# 8bit.net
KiCad netlist of a schematic drawn in EasyEDA
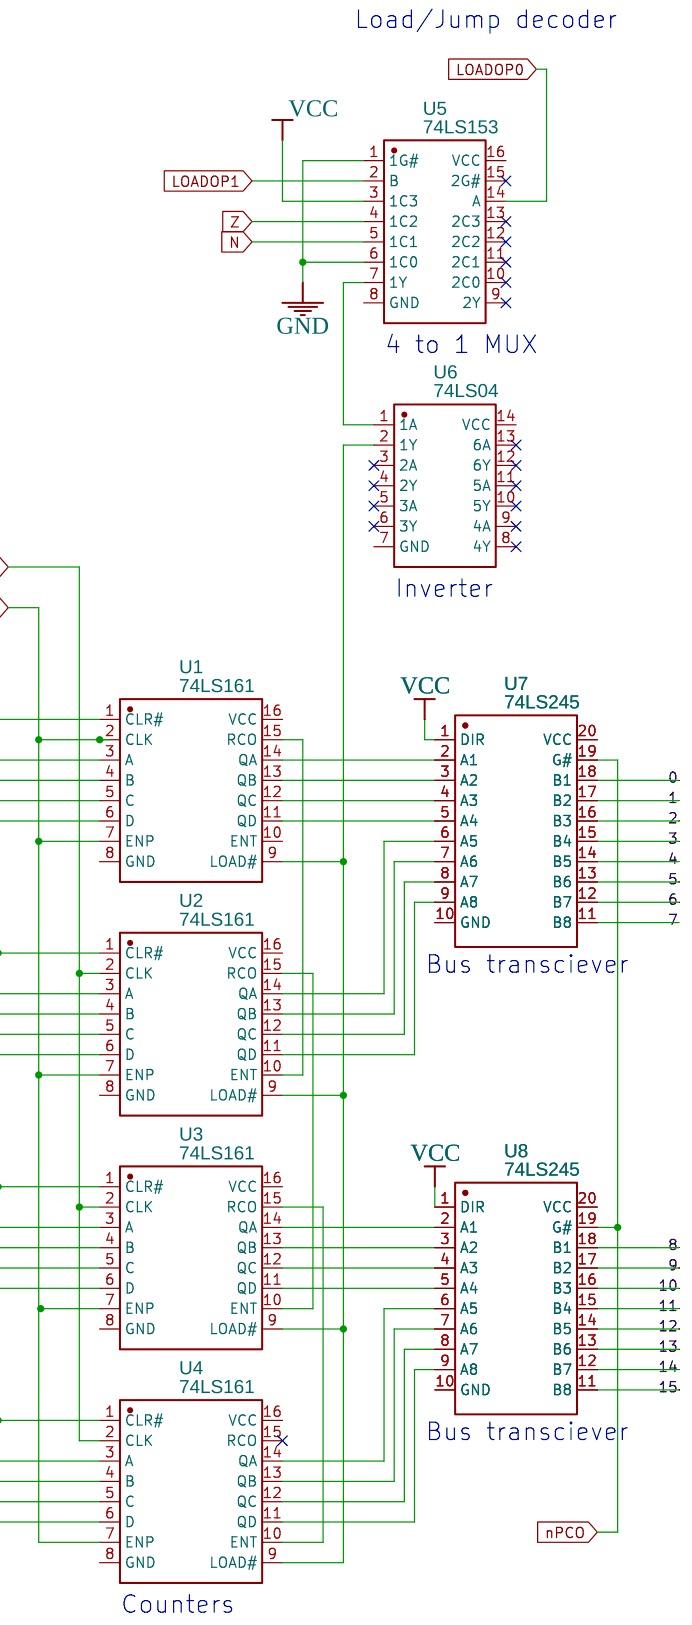
[diagram p0: PC]
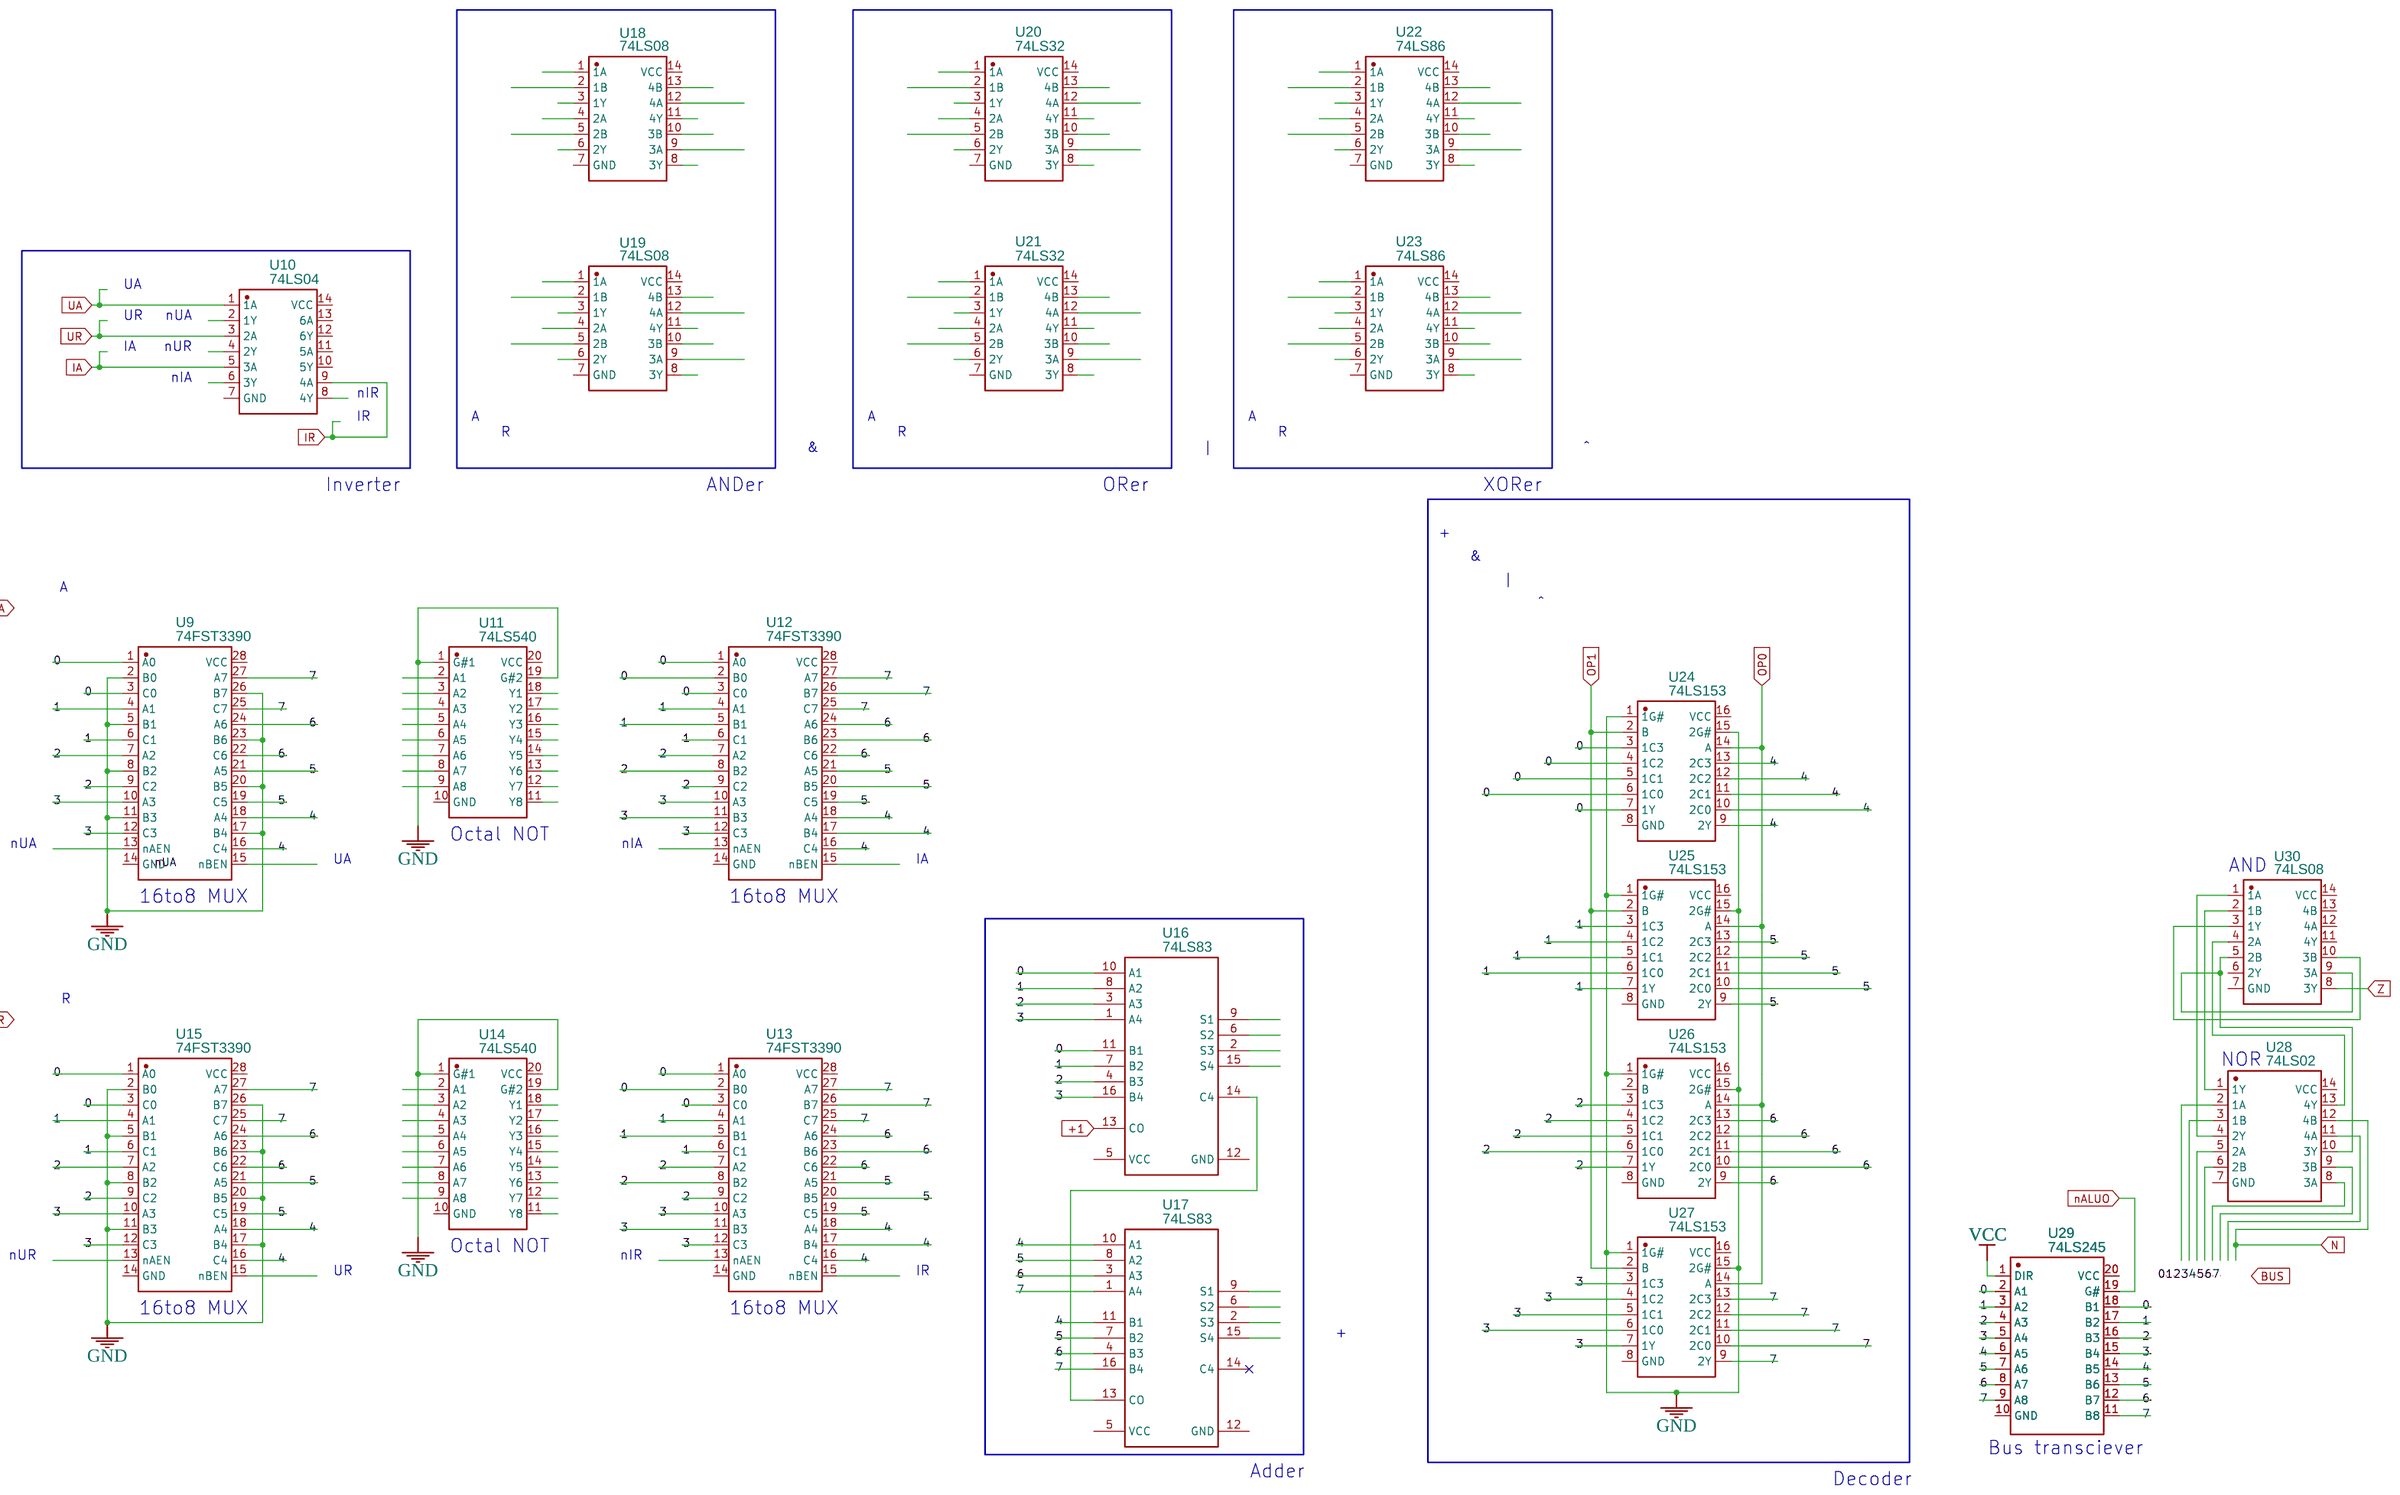
[diagram p1: ALU]

(export (version "E")
  (design (tool "Eeschema 10.0.6"))
  (components
    (comp (ref "U1")
      (value "74LS161")
      (fields
        (field (name "BOM_Manufacturer Part") "SN74LS161AN")
        (field (name "BOM_Supplier Part") "C1547960")
      )
      (libsource (lib "") (part "SN74LS161AN"))
    )
    (comp (ref "U2")
      (value "74LS161")
      (fields
        (field (name "BOM_Manufacturer Part") "SN74LS161AN")
        (field (name "BOM_Supplier Part") "C1547960")
      )
      (libsource (lib "") (part "SN74LS161AN"))
    )
    (comp (ref "U3")
      (value "74LS161")
      (fields
        (field (name "BOM_Manufacturer Part") "SN74LS161AN")
        (field (name "BOM_Supplier Part") "C1547960")
      )
      (libsource (lib "") (part "SN74LS161AN"))
    )
    (comp (ref "U4")
      (value "74LS161")
      (fields
        (field (name "BOM_Manufacturer Part") "SN74LS161AN")
        (field (name "BOM_Supplier Part") "C1547960")
      )
      (libsource (lib "") (part "SN74LS161AN"))
    )
    (comp (ref "U5")
      (value "74LS153")
      (fields
        (field (name "BOM_Manufacturer Part") "SN74LS153N")
        (field (name "BOM_Supplier Part") "C1547278")
      )
      (libsource (lib "") (part "SN74LS153N"))
    )
    (comp (ref "U6")
      (value "74LS04")
      (fields (field (name "BOM_Manufacturer Part") "XL74LS04") (field (name "BOM_Supplier Part") "C513511"))
      (libsource (lib "") (part "XL74LS04"))
    )
    (comp (ref "U7")
      (value "74LS245")
      (fields (field (name "BOM_Manufacturer Part") "74LS245WMX") (field (name "BOM_Supplier Part") "C6034"))
      (libsource (lib "") (part "74LS245WMX"))
    )
    (comp (ref "U8")
      (value "74LS245")
      (fields (field (name "BOM_Manufacturer Part") "74LS245WMX") (field (name "BOM_Supplier Part") "C6034"))
      (libsource (lib "") (part "74LS245WMX"))
    )
    (comp (ref "U9") (value "74FST3390") (libsource (lib "") (part "74FST3390")))
    (comp (ref "U10")
      (value "74LS04")
      (fields (field (name "BOM_Manufacturer Part") "XL74LS04") (field (name "BOM_Supplier Part") "C513511"))
      (libsource (lib "") (part "XL74LS04"))
    )
    (comp (ref "U11")
      (value "74LS540")
      (fields
        (field (name "BOM_Manufacturer Part") "SN74LS540DW")
        (field (name "BOM_Supplier Part") "C1548464")
      )
      (libsource (lib "") (part "SN74LS540DW"))
    )
    (comp (ref "U12") (value "74FST3390") (libsource (lib "") (part "74FST3390")))
    (comp (ref "U13") (value "74FST3390") (libsource (lib "") (part "74FST3390")))
    (comp (ref "U14")
      (value "74LS540")
      (fields
        (field (name "BOM_Manufacturer Part") "SN74LS540DW")
        (field (name "BOM_Supplier Part") "C1548464")
      )
      (libsource (lib "") (part "SN74LS540DW"))
    )
    (comp (ref "U15") (value "74FST3390") (libsource (lib "") (part "74FST3390")))
    (comp (ref "U16") (value "74LS83") (libsource (lib "") (part "HD74LS83AP")))
    (comp (ref "U17") (value "74LS83") (libsource (lib "") (part "HD74LS83AP")))
    (comp (ref "U18")
      (value "74LS08")
      (fields (field (name "BOM_Manufacturer Part") "XL74LS08") (field (name "BOM_Supplier Part") "C521140"))
      (libsource (lib "") (part "XL74LS08"))
    )
    (comp (ref "U19")
      (value "74LS08")
      (fields (field (name "BOM_Manufacturer Part") "XL74LS08") (field (name "BOM_Supplier Part") "C521140"))
      (libsource (lib "") (part "XL74LS08"))
    )
    (comp (ref "U20")
      (value "74LS32")
      (fields
        (field (name "BOM_Manufacturer Part") "SN74LS32D")
        (field (name "BOM_Supplier Part") "C2869302")
      )
      (libsource (lib "") (part "SN74LS32D"))
    )
    (comp (ref "U21")
      (value "74LS32")
      (fields
        (field (name "BOM_Manufacturer Part") "SN74LS32D")
        (field (name "BOM_Supplier Part") "C2869302")
      )
      (libsource (lib "") (part "SN74LS32D"))
    )
    (comp (ref "U22")
      (value "74LS86")
      (fields (field (name "BOM_Manufacturer Part") "XD74LS86") (field (name "BOM_Supplier Part") "C556290"))
      (libsource (lib "") (part "XD74LS86"))
    )
    (comp (ref "U23")
      (value "74LS86")
      (fields (field (name "BOM_Manufacturer Part") "XD74LS86") (field (name "BOM_Supplier Part") "C556290"))
      (libsource (lib "") (part "XD74LS86"))
    )
    (comp (ref "U24")
      (value "74LS153")
      (fields
        (field (name "BOM_Manufacturer Part") "SN74LS153D")
        (field (name "BOM_Supplier Part") "C1547147")
      )
      (libsource (lib "") (part "SN74LS153D"))
    )
    (comp (ref "U25")
      (value "74LS153")
      (fields
        (field (name "BOM_Manufacturer Part") "SN74LS153D")
        (field (name "BOM_Supplier Part") "C1547147")
      )
      (libsource (lib "") (part "SN74LS153D"))
    )
    (comp (ref "U26")
      (value "74LS153")
      (fields
        (field (name "BOM_Manufacturer Part") "SN74LS153D")
        (field (name "BOM_Supplier Part") "C1547147")
      )
      (libsource (lib "") (part "SN74LS153D"))
    )
    (comp (ref "U27")
      (value "74LS153")
      (fields
        (field (name "BOM_Manufacturer Part") "SN74LS153D")
        (field (name "BOM_Supplier Part") "C1547147")
      )
      (libsource (lib "") (part "SN74LS153D"))
    )
    (comp (ref "U28")
      (value "74LS02")
      (fields
        (field (name "BOM_Manufacturer Part") "SN74LS02D")
        (field (name "BOM_Supplier Part") "C2878666")
      )
      (libsource (lib "") (part "SN74LS02D"))
    )
    (comp (ref "U29")
      (value "74LS245")
      (fields (field (name "BOM_Manufacturer Part") "74LS245WMX") (field (name "BOM_Supplier Part") "C6034"))
      (libsource (lib "") (part "74LS245WMX"))
    )
    (comp (ref "U30")
      (value "74LS08")
      (fields (field (name "BOM_Manufacturer Part") "XL74LS08") (field (name "BOM_Supplier Part") "C521140"))
      (libsource (lib "") (part "XL74LS08"))
    )
  )
  (nets
    (net (code "1") (name "+1") (class "Default")
      (node (ref "U16") (pin "13") (pinfunction "CO_13") (pintype "unspecified"))
    )
    (net (code "2") (name "0") (class "Default")
      (node (ref "U1") (pin "3") (pinfunction "A_3") (pintype "unspecified"))
      (node (ref "U12") (pin "1") (pinfunction "A0_1") (pintype "unspecified"))
      (node (ref "U12") (pin "2") (pinfunction "B0_2") (pintype "unspecified"))
      (node (ref "U12") (pin "3") (pinfunction "C0_3") (pintype "unspecified"))
      (node (ref "U13") (pin "1") (pinfunction "A0_1") (pintype "unspecified"))
      (node (ref "U13") (pin "2") (pinfunction "B0_2") (pintype "unspecified"))
      (node (ref "U13") (pin "3") (pinfunction "C0_3") (pintype "unspecified"))
      (node (ref "U15") (pin "1") (pinfunction "A0_1") (pintype "unspecified"))
      (node (ref "U15") (pin "3") (pinfunction "C0_3") (pintype "unspecified"))
      (node (ref "U16") (pin "10") (pinfunction "A1_10") (pintype "unspecified"))
      (node (ref "U16") (pin "11") (pinfunction "B1_11") (pintype "unspecified"))
      (node (ref "U24") (pin "3") (pinfunction "1C3_3") (pintype "unspecified"))
      (node (ref "U24") (pin "4") (pinfunction "1C2_4") (pintype "unspecified"))
      (node (ref "U24") (pin "5") (pinfunction "1C1_5") (pintype "unspecified"))
      (node (ref "U24") (pin "6") (pinfunction "1C0_6") (pintype "unspecified"))
      (node (ref "U24") (pin "7") (pinfunction "1Y_7") (pintype "unspecified"))
      (node (ref "U29") (pin "18") (pinfunction "B1_18") (pintype "unspecified"))
      (node (ref "U29") (pin "2") (pinfunction "A1_2") (pintype "unspecified"))
      (node (ref "U7") (pin "18") (pinfunction "B1_18") (pintype "unspecified"))
      (node (ref "U9") (pin "1") (pinfunction "A0_1") (pintype "unspecified"))
      (node (ref "U9") (pin "3") (pinfunction "C0_3") (pintype "unspecified"))
    )
    (net (code "3") (name "1") (class "Default")
      (node (ref "U1") (pin "4") (pinfunction "B_4") (pintype "unspecified"))
      (node (ref "U12") (pin "4") (pinfunction "A1_4") (pintype "unspecified"))
      (node (ref "U12") (pin "5") (pinfunction "B1_5") (pintype "unspecified"))
      (node (ref "U12") (pin "6") (pinfunction "C1_6") (pintype "unspecified"))
      (node (ref "U13") (pin "4") (pinfunction "A1_4") (pintype "unspecified"))
      (node (ref "U13") (pin "5") (pinfunction "B1_5") (pintype "unspecified"))
      (node (ref "U13") (pin "6") (pinfunction "C1_6") (pintype "unspecified"))
      (node (ref "U15") (pin "4") (pinfunction "A1_4") (pintype "unspecified"))
      (node (ref "U15") (pin "6") (pinfunction "C1_6") (pintype "unspecified"))
      (node (ref "U16") (pin "7") (pinfunction "B2_7") (pintype "unspecified"))
      (node (ref "U16") (pin "8") (pinfunction "A2_8") (pintype "unspecified"))
      (node (ref "U25") (pin "3") (pinfunction "1C3_3") (pintype "unspecified"))
      (node (ref "U25") (pin "4") (pinfunction "1C2_4") (pintype "unspecified"))
      (node (ref "U25") (pin "5") (pinfunction "1C1_5") (pintype "unspecified"))
      (node (ref "U25") (pin "6") (pinfunction "1C0_6") (pintype "unspecified"))
      (node (ref "U25") (pin "7") (pinfunction "1Y_7") (pintype "unspecified"))
      (node (ref "U29") (pin "17") (pinfunction "B2_17") (pintype "unspecified"))
      (node (ref "U29") (pin "3") (pinfunction "A2_3") (pintype "unspecified"))
      (node (ref "U7") (pin "17") (pinfunction "B2_17") (pintype "unspecified"))
      (node (ref "U9") (pin "4") (pinfunction "A1_4") (pintype "unspecified"))
      (node (ref "U9") (pin "6") (pinfunction "C1_6") (pintype "unspecified"))
    )
    (net (code "4") (name "2") (class "Default")
      (node (ref "U1") (pin "5") (pinfunction "C_5") (pintype "unspecified"))
      (node (ref "U12") (pin "7") (pinfunction "A2_7") (pintype "unspecified"))
      (node (ref "U12") (pin "8") (pinfunction "B2_8") (pintype "unspecified"))
      (node (ref "U12") (pin "9") (pinfunction "C2_9") (pintype "unspecified"))
      (node (ref "U13") (pin "7") (pinfunction "A2_7") (pintype "unspecified"))
      (node (ref "U13") (pin "8") (pinfunction "B2_8") (pintype "unspecified"))
      (node (ref "U13") (pin "9") (pinfunction "C2_9") (pintype "unspecified"))
      (node (ref "U15") (pin "7") (pinfunction "A2_7") (pintype "unspecified"))
      (node (ref "U15") (pin "9") (pinfunction "C2_9") (pintype "unspecified"))
      (node (ref "U16") (pin "3") (pinfunction "A3_3") (pintype "unspecified"))
      (node (ref "U16") (pin "4") (pinfunction "B3_4") (pintype "unspecified"))
      (node (ref "U26") (pin "3") (pinfunction "1C3_3") (pintype "unspecified"))
      (node (ref "U26") (pin "4") (pinfunction "1C2_4") (pintype "unspecified"))
      (node (ref "U26") (pin "5") (pinfunction "1C1_5") (pintype "unspecified"))
      (node (ref "U26") (pin "6") (pinfunction "1C0_6") (pintype "unspecified"))
      (node (ref "U26") (pin "7") (pinfunction "1Y_7") (pintype "unspecified"))
      (node (ref "U29") (pin "16") (pinfunction "B3_16") (pintype "unspecified"))
      (node (ref "U29") (pin "4") (pinfunction "A3_4") (pintype "unspecified"))
      (node (ref "U7") (pin "16") (pinfunction "B3_16") (pintype "unspecified"))
      (node (ref "U9") (pin "7") (pinfunction "A2_7") (pintype "unspecified"))
      (node (ref "U9") (pin "9") (pinfunction "C2_9") (pintype "unspecified"))
    )
    (net (code "5") (name "3") (class "Default")
      (node (ref "U1") (pin "6") (pinfunction "D_6") (pintype "unspecified"))
      (node (ref "U12") (pin "10") (pinfunction "A3_10") (pintype "unspecified"))
      (node (ref "U12") (pin "11") (pinfunction "B3_11") (pintype "unspecified"))
      (node (ref "U12") (pin "12") (pinfunction "C3_12") (pintype "unspecified"))
      (node (ref "U13") (pin "10") (pinfunction "A3_10") (pintype "unspecified"))
      (node (ref "U13") (pin "11") (pinfunction "B3_11") (pintype "unspecified"))
      (node (ref "U13") (pin "12") (pinfunction "C3_12") (pintype "unspecified"))
      (node (ref "U15") (pin "10") (pinfunction "A3_10") (pintype "unspecified"))
      (node (ref "U15") (pin "12") (pinfunction "C3_12") (pintype "unspecified"))
      (node (ref "U16") (pin "1") (pinfunction "A4_1") (pintype "unspecified"))
      (node (ref "U16") (pin "16") (pinfunction "B4_16") (pintype "unspecified"))
      (node (ref "U27") (pin "3") (pinfunction "1C3_3") (pintype "unspecified"))
      (node (ref "U27") (pin "4") (pinfunction "1C2_4") (pintype "unspecified"))
      (node (ref "U27") (pin "5") (pinfunction "1C1_5") (pintype "unspecified"))
      (node (ref "U27") (pin "6") (pinfunction "1C0_6") (pintype "unspecified"))
      (node (ref "U27") (pin "7") (pinfunction "1Y_7") (pintype "unspecified"))
      (node (ref "U29") (pin "15") (pinfunction "B4_15") (pintype "unspecified"))
      (node (ref "U29") (pin "5") (pinfunction "A4_5") (pintype "unspecified"))
      (node (ref "U7") (pin "15") (pinfunction "B4_15") (pintype "unspecified"))
      (node (ref "U9") (pin "10") (pinfunction "A3_10") (pintype "unspecified"))
      (node (ref "U9") (pin "12") (pinfunction "C3_12") (pintype "unspecified"))
    )
    (net (code "6") (name "4") (class "Default")
      (node (ref "U12") (pin "16") (pinfunction "C4_16") (pintype "unspecified"))
      (node (ref "U12") (pin "17") (pinfunction "B4_17") (pintype "unspecified"))
      (node (ref "U12") (pin "18") (pinfunction "A4_18") (pintype "unspecified"))
      (node (ref "U13") (pin "16") (pinfunction "C4_16") (pintype "unspecified"))
      (node (ref "U13") (pin "17") (pinfunction "B4_17") (pintype "unspecified"))
      (node (ref "U13") (pin "18") (pinfunction "A4_18") (pintype "unspecified"))
      (node (ref "U15") (pin "16") (pinfunction "C4_16") (pintype "unspecified"))
      (node (ref "U15") (pin "18") (pinfunction "A4_18") (pintype "unspecified"))
      (node (ref "U17") (pin "10") (pinfunction "A1_10") (pintype "unspecified"))
      (node (ref "U17") (pin "11") (pinfunction "B1_11") (pintype "unspecified"))
      (node (ref "U2") (pin "3") (pinfunction "A_3") (pintype "unspecified"))
      (node (ref "U24") (pin "10") (pinfunction "2C0_10") (pintype "unspecified"))
      (node (ref "U24") (pin "11") (pinfunction "2C1_11") (pintype "unspecified"))
      (node (ref "U24") (pin "12") (pinfunction "2C2_12") (pintype "unspecified"))
      (node (ref "U24") (pin "13") (pinfunction "2C3_13") (pintype "unspecified"))
      (node (ref "U24") (pin "9") (pinfunction "2Y_9") (pintype "unspecified"))
      (node (ref "U29") (pin "14") (pinfunction "B5_14") (pintype "unspecified"))
      (node (ref "U29") (pin "6") (pinfunction "A5_6") (pintype "unspecified"))
      (node (ref "U7") (pin "14") (pinfunction "B5_14") (pintype "unspecified"))
      (node (ref "U9") (pin "16") (pinfunction "C4_16") (pintype "unspecified"))
      (node (ref "U9") (pin "18") (pinfunction "A4_18") (pintype "unspecified"))
    )
    (net (code "7") (name "5") (class "Default")
      (node (ref "U12") (pin "19") (pinfunction "C5_19") (pintype "unspecified"))
      (node (ref "U12") (pin "20") (pinfunction "B5_20") (pintype "unspecified"))
      (node (ref "U12") (pin "21") (pinfunction "A5_21") (pintype "unspecified"))
      (node (ref "U13") (pin "19") (pinfunction "C5_19") (pintype "unspecified"))
      (node (ref "U13") (pin "20") (pinfunction "B5_20") (pintype "unspecified"))
      (node (ref "U13") (pin "21") (pinfunction "A5_21") (pintype "unspecified"))
      (node (ref "U15") (pin "19") (pinfunction "C5_19") (pintype "unspecified"))
      (node (ref "U15") (pin "21") (pinfunction "A5_21") (pintype "unspecified"))
      (node (ref "U17") (pin "7") (pinfunction "B2_7") (pintype "unspecified"))
      (node (ref "U17") (pin "8") (pinfunction "A2_8") (pintype "unspecified"))
      (node (ref "U2") (pin "4") (pinfunction "B_4") (pintype "unspecified"))
      (node (ref "U25") (pin "10") (pinfunction "2C0_10") (pintype "unspecified"))
      (node (ref "U25") (pin "11") (pinfunction "2C1_11") (pintype "unspecified"))
      (node (ref "U25") (pin "12") (pinfunction "2C2_12") (pintype "unspecified"))
      (node (ref "U25") (pin "13") (pinfunction "2C3_13") (pintype "unspecified"))
      (node (ref "U25") (pin "9") (pinfunction "2Y_9") (pintype "unspecified"))
      (node (ref "U29") (pin "13") (pinfunction "B6_13") (pintype "unspecified"))
      (node (ref "U29") (pin "7") (pinfunction "A6_7") (pintype "unspecified"))
      (node (ref "U7") (pin "13") (pinfunction "B6_13") (pintype "unspecified"))
      (node (ref "U9") (pin "19") (pinfunction "C5_19") (pintype "unspecified"))
      (node (ref "U9") (pin "21") (pinfunction "A5_21") (pintype "unspecified"))
    )
    (net (code "8") (name "6") (class "Default")
      (node (ref "U12") (pin "22") (pinfunction "C6_22") (pintype "unspecified"))
      (node (ref "U12") (pin "23") (pinfunction "B6_23") (pintype "unspecified"))
      (node (ref "U12") (pin "24") (pinfunction "A6_24") (pintype "unspecified"))
      (node (ref "U13") (pin "22") (pinfunction "C6_22") (pintype "unspecified"))
      (node (ref "U13") (pin "23") (pinfunction "B6_23") (pintype "unspecified"))
      (node (ref "U13") (pin "24") (pinfunction "A6_24") (pintype "unspecified"))
      (node (ref "U15") (pin "22") (pinfunction "C6_22") (pintype "unspecified"))
      (node (ref "U15") (pin "24") (pinfunction "A6_24") (pintype "unspecified"))
      (node (ref "U17") (pin "3") (pinfunction "A3_3") (pintype "unspecified"))
      (node (ref "U17") (pin "4") (pinfunction "B3_4") (pintype "unspecified"))
      (node (ref "U2") (pin "5") (pinfunction "C_5") (pintype "unspecified"))
      (node (ref "U26") (pin "10") (pinfunction "2C0_10") (pintype "unspecified"))
      (node (ref "U26") (pin "11") (pinfunction "2C1_11") (pintype "unspecified"))
      (node (ref "U26") (pin "12") (pinfunction "2C2_12") (pintype "unspecified"))
      (node (ref "U26") (pin "13") (pinfunction "2C3_13") (pintype "unspecified"))
      (node (ref "U26") (pin "9") (pinfunction "2Y_9") (pintype "unspecified"))
      (node (ref "U29") (pin "12") (pinfunction "B7_12") (pintype "unspecified"))
      (node (ref "U29") (pin "8") (pinfunction "A7_8") (pintype "unspecified"))
      (node (ref "U7") (pin "12") (pinfunction "B7_12") (pintype "unspecified"))
      (node (ref "U9") (pin "22") (pinfunction "C6_22") (pintype "unspecified"))
      (node (ref "U9") (pin "24") (pinfunction "A6_24") (pintype "unspecified"))
    )
    (net (code "9") (name "7") (class "Default")
      (node (ref "U12") (pin "25") (pinfunction "C7_25") (pintype "unspecified"))
      (node (ref "U12") (pin "26") (pinfunction "B7_26") (pintype "unspecified"))
      (node (ref "U12") (pin "27") (pinfunction "A7_27") (pintype "unspecified"))
      (node (ref "U13") (pin "25") (pinfunction "C7_25") (pintype "unspecified"))
      (node (ref "U13") (pin "26") (pinfunction "B7_26") (pintype "unspecified"))
      (node (ref "U13") (pin "27") (pinfunction "A7_27") (pintype "unspecified"))
      (node (ref "U15") (pin "25") (pinfunction "C7_25") (pintype "unspecified"))
      (node (ref "U15") (pin "27") (pinfunction "A7_27") (pintype "unspecified"))
      (node (ref "U17") (pin "1") (pinfunction "A4_1") (pintype "unspecified"))
      (node (ref "U17") (pin "16") (pinfunction "B4_16") (pintype "unspecified"))
      (node (ref "U2") (pin "6") (pinfunction "D_6") (pintype "unspecified"))
      (node (ref "U27") (pin "10") (pinfunction "2C0_10") (pintype "unspecified"))
      (node (ref "U27") (pin "11") (pinfunction "2C1_11") (pintype "unspecified"))
      (node (ref "U27") (pin "12") (pinfunction "2C2_12") (pintype "unspecified"))
      (node (ref "U27") (pin "13") (pinfunction "2C3_13") (pintype "unspecified"))
      (node (ref "U27") (pin "9") (pinfunction "2Y_9") (pintype "unspecified"))
      (node (ref "U29") (pin "11") (pinfunction "B8_11") (pintype "unspecified"))
      (node (ref "U29") (pin "9") (pinfunction "A8_9") (pintype "unspecified"))
      (node (ref "U7") (pin "11") (pinfunction "B8_11") (pintype "unspecified"))
      (node (ref "U9") (pin "25") (pinfunction "C7_25") (pintype "unspecified"))
      (node (ref "U9") (pin "27") (pinfunction "A7_27") (pintype "unspecified"))
    )
    (net (code "10") (name "8") (class "Default")
      (node (ref "U3") (pin "3") (pinfunction "A_3") (pintype "unspecified"))
      (node (ref "U8") (pin "18") (pinfunction "B1_18") (pintype "unspecified"))
    )
    (net (code "11") (name "9") (class "Default")
      (node (ref "U3") (pin "4") (pinfunction "B_4") (pintype "unspecified"))
      (node (ref "U8") (pin "17") (pinfunction "B2_17") (pintype "unspecified"))
    )
    (net (code "12") (name "10") (class "Default")
      (node (ref "U3") (pin "5") (pinfunction "C_5") (pintype "unspecified"))
      (node (ref "U8") (pin "16") (pinfunction "B3_16") (pintype "unspecified"))
    )
    (net (code "13") (name "11") (class "Default")
      (node (ref "U3") (pin "6") (pinfunction "D_6") (pintype "unspecified"))
      (node (ref "U8") (pin "15") (pinfunction "B4_15") (pintype "unspecified"))
    )
    (net (code "14") (name "12") (class "Default")
      (node (ref "U4") (pin "3") (pinfunction "A_3") (pintype "unspecified"))
      (node (ref "U8") (pin "14") (pinfunction "B5_14") (pintype "unspecified"))
    )
    (net (code "15") (name "13") (class "Default")
      (node (ref "U4") (pin "4") (pinfunction "B_4") (pintype "unspecified"))
      (node (ref "U8") (pin "13") (pinfunction "B6_13") (pintype "unspecified"))
    )
    (net (code "16") (name "14") (class "Default")
      (node (ref "U4") (pin "5") (pinfunction "C_5") (pintype "unspecified"))
      (node (ref "U8") (pin "12") (pinfunction "B7_12") (pintype "unspecified"))
    )
    (net (code "17") (name "15") (class "Default")
      (node (ref "U4") (pin "6") (pinfunction "D_6") (pintype "unspecified"))
      (node (ref "U8") (pin "11") (pinfunction "B8_11") (pintype "unspecified"))
    )
    (net (code "20") (name "CLK") (class "Default")
      (node (ref "U2") (pin "2") (pinfunction "CLK_2") (pintype "unspecified"))
      (node (ref "U3") (pin "2") (pinfunction "CLK_2") (pintype "unspecified"))
      (node (ref "U4") (pin "2") (pinfunction "CLK_2") (pintype "unspecified"))
    )
    (net (code "21") (name "GND") (class "Default")
      (node (ref "U11") (pin "1") (pinfunction "G#1_1") (pintype "unspecified"))
      (node (ref "U11") (pin "19") (pinfunction "G#2_19") (pintype "unspecified"))
      (node (ref "U14") (pin "1") (pinfunction "G#1_1") (pintype "unspecified"))
      (node (ref "U14") (pin "19") (pinfunction "G#2_19") (pintype "unspecified"))
      (node (ref "U15") (pin "11") (pinfunction "B3_11") (pintype "unspecified"))
      (node (ref "U15") (pin "17") (pinfunction "B4_17") (pintype "unspecified"))
      (node (ref "U15") (pin "2") (pinfunction "B0_2") (pintype "unspecified"))
      (node (ref "U15") (pin "20") (pinfunction "B5_20") (pintype "unspecified"))
      (node (ref "U15") (pin "23") (pinfunction "B6_23") (pintype "unspecified"))
      (node (ref "U15") (pin "26") (pinfunction "B7_26") (pintype "unspecified"))
      (node (ref "U15") (pin "5") (pinfunction "B1_5") (pintype "unspecified"))
      (node (ref "U15") (pin "8") (pinfunction "B2_8") (pintype "unspecified"))
      (node (ref "U24") (pin "1") (pinfunction "1G#_1") (pintype "unspecified"))
      (node (ref "U24") (pin "15") (pinfunction "2G#_15") (pintype "unspecified"))
      (node (ref "U25") (pin "1") (pinfunction "1G#_1") (pintype "unspecified"))
      (node (ref "U25") (pin "15") (pinfunction "2G#_15") (pintype "unspecified"))
      (node (ref "U26") (pin "1") (pinfunction "1G#_1") (pintype "unspecified"))
      (node (ref "U26") (pin "15") (pinfunction "2G#_15") (pintype "unspecified"))
      (node (ref "U27") (pin "1") (pinfunction "1G#_1") (pintype "unspecified"))
      (node (ref "U27") (pin "15") (pinfunction "2G#_15") (pintype "unspecified"))
      (node (ref "U5") (pin "1") (pinfunction "1G#_1") (pintype "unspecified"))
      (node (ref "U5") (pin "6") (pinfunction "1C0_6") (pintype "unspecified"))
      (node (ref "U9") (pin "11") (pinfunction "B3_11") (pintype "unspecified"))
      (node (ref "U9") (pin "17") (pinfunction "B4_17") (pintype "unspecified"))
      (node (ref "U9") (pin "2") (pinfunction "B0_2") (pintype "unspecified"))
      (node (ref "U9") (pin "20") (pinfunction "B5_20") (pintype "unspecified"))
      (node (ref "U9") (pin "23") (pinfunction "B6_23") (pintype "unspecified"))
      (node (ref "U9") (pin "26") (pinfunction "B7_26") (pintype "unspecified"))
      (node (ref "U9") (pin "5") (pinfunction "B1_5") (pintype "unspecified"))
      (node (ref "U9") (pin "8") (pinfunction "B2_8") (pintype "unspecified"))
    )
    (net (code "22") (name "IA") (class "Default")
      (node (ref "U10") (pin "5") (pinfunction "3A_5") (pintype "unspecified"))
    )
    (net (code "23") (name "INC") (class "Default")
      (node (ref "U1") (pin "2") (pinfunction "CLK_2") (pintype "unspecified"))
      (node (ref "U1") (pin "7") (pinfunction "ENP_7") (pintype "unspecified"))
      (node (ref "U2") (pin "7") (pinfunction "ENP_7") (pintype "unspecified"))
      (node (ref "U3") (pin "7") (pinfunction "ENP_7") (pintype "unspecified"))
      (node (ref "U4") (pin "7") (pinfunction "ENP_7") (pintype "unspecified"))
    )
    (net (code "24") (name "IR") (class "Default")
      (node (ref "U10") (pin "9") (pinfunction "4A_9") (pintype "unspecified"))
    )
    (net (code "25") (name "LOADOP0") (class "Default")
      (node (ref "U5") (pin "14") (pinfunction "A_14") (pintype "unspecified"))
    )
    (net (code "26") (name "LOADOP1") (class "Default")
      (node (ref "U5") (pin "2") (pinfunction "B_2") (pintype "unspecified"))
    )
    (net (code "27") (name "N") (class "Default")
      (node (ref "U28") (pin "12") (pinfunction "4B_12") (pintype "unspecified"))
      (node (ref "U5") (pin "5") (pinfunction "1C1_5") (pintype "unspecified"))
    )
    (net (code "28") (name "Net-(U1-LOAD#)") (class "Default")
      (node (ref "U1") (pin "9") (pinfunction "LOAD#_9") (pintype "unspecified"))
      (node (ref "U2") (pin "9") (pinfunction "LOAD#_9") (pintype "unspecified"))
      (node (ref "U3") (pin "9") (pinfunction "LOAD#_9") (pintype "unspecified"))
      (node (ref "U4") (pin "9") (pinfunction "LOAD#_9") (pintype "unspecified"))
      (node (ref "U6") (pin "2") (pinfunction "1Y_2") (pintype "unspecified"))
    )
    (net (code "29") (name "Net-(U1-QA)") (class "Default")
      (node (ref "U1") (pin "14") (pinfunction "QA_14") (pintype "unspecified"))
      (node (ref "U7") (pin "2") (pinfunction "A1_2") (pintype "unspecified"))
    )
    (net (code "30") (name "Net-(U1-QB)") (class "Default")
      (node (ref "U1") (pin "13") (pinfunction "QB_13") (pintype "unspecified"))
      (node (ref "U7") (pin "3") (pinfunction "A2_3") (pintype "unspecified"))
    )
    (net (code "31") (name "Net-(U1-QC)") (class "Default")
      (node (ref "U1") (pin "12") (pinfunction "QC_12") (pintype "unspecified"))
      (node (ref "U7") (pin "4") (pinfunction "A3_4") (pintype "unspecified"))
    )
    (net (code "32") (name "Net-(U1-QD)") (class "Default")
      (node (ref "U1") (pin "11") (pinfunction "QD_11") (pintype "unspecified"))
      (node (ref "U7") (pin "5") (pinfunction "A4_5") (pintype "unspecified"))
    )
    (net (code "33") (name "Net-(U1-RCO)") (class "Default")
      (node (ref "U1") (pin "15") (pinfunction "RCO_15") (pintype "unspecified"))
      (node (ref "U2") (pin "10") (pinfunction "ENT_10") (pintype "unspecified"))
    )
    (net (code "34") (name "Net-(U2-QA)") (class "Default")
      (node (ref "U2") (pin "14") (pinfunction "QA_14") (pintype "unspecified"))
      (node (ref "U7") (pin "6") (pinfunction "A5_6") (pintype "unspecified"))
    )
    (net (code "35") (name "Net-(U2-QB)") (class "Default")
      (node (ref "U2") (pin "13") (pinfunction "QB_13") (pintype "unspecified"))
      (node (ref "U7") (pin "7") (pinfunction "A6_7") (pintype "unspecified"))
    )
    (net (code "36") (name "Net-(U2-QC)") (class "Default")
      (node (ref "U2") (pin "12") (pinfunction "QC_12") (pintype "unspecified"))
      (node (ref "U7") (pin "8") (pinfunction "A7_8") (pintype "unspecified"))
    )
    (net (code "37") (name "Net-(U2-QD)") (class "Default")
      (node (ref "U2") (pin "11") (pinfunction "QD_11") (pintype "unspecified"))
      (node (ref "U7") (pin "9") (pinfunction "A8_9") (pintype "unspecified"))
    )
    (net (code "38") (name "Net-(U2-RCO)") (class "Default")
      (node (ref "U2") (pin "15") (pinfunction "RCO_15") (pintype "unspecified"))
      (node (ref "U3") (pin "10") (pinfunction "ENT_10") (pintype "unspecified"))
    )
    (net (code "39") (name "Net-(U3-QA)") (class "Default")
      (node (ref "U3") (pin "14") (pinfunction "QA_14") (pintype "unspecified"))
      (node (ref "U8") (pin "2") (pinfunction "A1_2") (pintype "unspecified"))
    )
    (net (code "40") (name "Net-(U3-QB)") (class "Default")
      (node (ref "U3") (pin "13") (pinfunction "QB_13") (pintype "unspecified"))
      (node (ref "U8") (pin "3") (pinfunction "A2_3") (pintype "unspecified"))
    )
    (net (code "41") (name "Net-(U3-QC)") (class "Default")
      (node (ref "U3") (pin "12") (pinfunction "QC_12") (pintype "unspecified"))
      (node (ref "U8") (pin "4") (pinfunction "A3_4") (pintype "unspecified"))
    )
    (net (code "42") (name "Net-(U3-QD)") (class "Default")
      (node (ref "U3") (pin "11") (pinfunction "QD_11") (pintype "unspecified"))
      (node (ref "U8") (pin "5") (pinfunction "A4_5") (pintype "unspecified"))
    )
    (net (code "43") (name "Net-(U3-RCO)") (class "Default")
      (node (ref "U3") (pin "15") (pinfunction "RCO_15") (pintype "unspecified"))
      (node (ref "U4") (pin "10") (pinfunction "ENT_10") (pintype "unspecified"))
    )
    (net (code "44") (name "Net-(U4-QA)") (class "Default")
      (node (ref "U4") (pin "14") (pinfunction "QA_14") (pintype "unspecified"))
      (node (ref "U8") (pin "6") (pinfunction "A5_6") (pintype "unspecified"))
    )
    (net (code "45") (name "Net-(U4-QB)") (class "Default")
      (node (ref "U4") (pin "13") (pinfunction "QB_13") (pintype "unspecified"))
      (node (ref "U8") (pin "7") (pinfunction "A6_7") (pintype "unspecified"))
    )
    (net (code "46") (name "Net-(U4-QC)") (class "Default")
      (node (ref "U4") (pin "12") (pinfunction "QC_12") (pintype "unspecified"))
      (node (ref "U8") (pin "8") (pinfunction "A7_8") (pintype "unspecified"))
    )
    (net (code "47") (name "Net-(U4-QD)") (class "Default")
      (node (ref "U4") (pin "11") (pinfunction "QD_11") (pintype "unspecified"))
      (node (ref "U8") (pin "9") (pinfunction "A8_9") (pintype "unspecified"))
    )
    (net (code "48") (name "Net-(U5-1Y)") (class "Default")
      (node (ref "U5") (pin "7") (pinfunction "1Y_7") (pintype "unspecified"))
      (node (ref "U6") (pin "1") (pinfunction "1A_1") (pintype "unspecified"))
    )
    (net (code "49") (name "Net-(U16-C4)") (class "Default")
      (node (ref "U16") (pin "14") (pinfunction "C4_14") (pintype "output"))
      (node (ref "U17") (pin "13") (pinfunction "CO_13") (pintype "unspecified"))
    )
    (net (code "50") (name "Net-(U28-1Y)") (class "Default")
      (node (ref "U28") (pin "1") (pinfunction "1Y_1") (pintype "unspecified"))
      (node (ref "U30") (pin "2") (pinfunction "1B_2") (pintype "unspecified"))
    )
    (net (code "51") (name "Net-(U28-2Y)") (class "Default")
      (node (ref "U28") (pin "4") (pinfunction "2Y_4") (pintype "unspecified"))
      (node (ref "U30") (pin "1") (pinfunction "1A_1") (pintype "unspecified"))
    )
    (net (code "52") (name "Net-(U28-3Y)") (class "Default")
      (node (ref "U28") (pin "10") (pinfunction "3Y_10") (pintype "unspecified"))
      (node (ref "U30") (pin "5") (pinfunction "2B_5") (pintype "unspecified"))
      (node (ref "U30") (pin "9") (pinfunction "3A_9") (pintype "unspecified"))
    )
    (net (code "53") (name "Net-(U28-4Y)") (class "Default")
      (node (ref "U28") (pin "13") (pinfunction "4Y_13") (pintype "unspecified"))
      (node (ref "U30") (pin "4") (pinfunction "2A_4") (pintype "unspecified"))
    )
    (net (code "54") (name "Net-(U30-1Y)") (class "Default")
      (node (ref "U30") (pin "10") (pinfunction "3B_10") (pintype "unspecified"))
      (node (ref "U30") (pin "3") (pinfunction "1Y_3") (pintype "unspecified"))
    )
    (net (code "55") (name "OP0") (class "Default")
      (node (ref "U24") (pin "14") (pinfunction "A_14") (pintype "unspecified"))
      (node (ref "U25") (pin "14") (pinfunction "A_14") (pintype "unspecified"))
      (node (ref "U26") (pin "14") (pinfunction "A_14") (pintype "unspecified"))
      (node (ref "U27") (pin "14") (pinfunction "A_14") (pintype "unspecified"))
    )
    (net (code "56") (name "OP1") (class "Default")
      (node (ref "U24") (pin "2") (pinfunction "B_2") (pintype "unspecified"))
      (node (ref "U25") (pin "2") (pinfunction "B_2") (pintype "unspecified"))
      (node (ref "U27") (pin "2") (pinfunction "B_2") (pintype "unspecified"))
    )
    (net (code "58") (name "UA") (class "Default")
      (node (ref "U10") (pin "1") (pinfunction "1A_1") (pintype "unspecified"))
    )
    (net (code "59") (name "UR") (class "Default")
      (node (ref "U10") (pin "3") (pinfunction "2A_3") (pintype "unspecified"))
    )
    (net (code "60") (name "VCC") (class "Default")
      (node (ref "U29") (pin "1") (pinfunction "DIR_1") (pintype "unspecified"))
      (node (ref "U5") (pin "3") (pinfunction "1C3_3") (pintype "unspecified"))
      (node (ref "U7") (pin "1") (pinfunction "DIR_1") (pintype "unspecified"))
      (node (ref "U8") (pin "1") (pinfunction "DIR_1") (pintype "unspecified"))
    )
    (net (code "61") (name "Z") (class "Default")
      (node (ref "U30") (pin "8") (pinfunction "3Y_8") (pintype "unspecified"))
      (node (ref "U5") (pin "4") (pinfunction "1C2_4") (pintype "unspecified"))
    )
    (net (code "62") (name "nALUO") (class "Default")
      (node (ref "U29") (pin "19") (pinfunction "G#_19") (pintype "unspecified"))
    )
    (net (code "63") (name "nCLR") (class "Default")
      (node (ref "U1") (pin "1") (pinfunction "CLR#_1") (pintype "unspecified"))
      (node (ref "U2") (pin "1") (pinfunction "CLR#_1") (pintype "unspecified"))
      (node (ref "U3") (pin "1") (pinfunction "CLR#_1") (pintype "unspecified"))
      (node (ref "U4") (pin "1") (pinfunction "CLR#_1") (pintype "unspecified"))
    )
    (net (code "64") (name "nPCO") (class "Default")
      (node (ref "U7") (pin "19") (pinfunction "G#_19") (pintype "unspecified"))
      (node (ref "U8") (pin "19") (pinfunction "G#_19") (pintype "unspecified"))
    )
    (net (code "66") (name "unconnected-(U1-ENT-Pad10)") (class "Default")
      (node (ref "U1") (pin "10") (pinfunction "ENT_10") (pintype "unspecified"))
    )
    (net (code "67") (name "unconnected-(U1-GND-Pad8)") (class "Default")
      (node (ref "U1") (pin "8") (pinfunction "GND_8") (pintype "passive"))
    )
    (net (code "68") (name "unconnected-(U1-VCC-Pad16)") (class "Default")
      (node (ref "U1") (pin "16") (pinfunction "VCC_16") (pintype "passive"))
    )
    (net (code "69") (name "unconnected-(U2-GND-Pad8)") (class "Default")
      (node (ref "U2") (pin "8") (pinfunction "GND_8") (pintype "passive"))
    )
    (net (code "70") (name "unconnected-(U2-VCC-Pad16)") (class "Default")
      (node (ref "U2") (pin "16") (pinfunction "VCC_16") (pintype "passive"))
    )
    (net (code "71") (name "unconnected-(U3-GND-Pad8)") (class "Default")
      (node (ref "U3") (pin "8") (pinfunction "GND_8") (pintype "passive"))
    )
    (net (code "72") (name "unconnected-(U3-VCC-Pad16)") (class "Default")
      (node (ref "U3") (pin "16") (pinfunction "VCC_16") (pintype "passive"))
    )
    (net (code "73") (name "unconnected-(U4-GND-Pad8)") (class "Default")
      (node (ref "U4") (pin "8") (pinfunction "GND_8") (pintype "passive"))
    )
    (net (code "74") (name "unconnected-(U4-RCO-Pad15)") (class "Default")
      (node (ref "U4") (pin "15") (pinfunction "RCO_15") (pintype "unspecified+no_connect"))
    )
    (net (code "75") (name "unconnected-(U4-VCC-Pad16)") (class "Default")
      (node (ref "U4") (pin "16") (pinfunction "VCC_16") (pintype "passive"))
    )
    (net (code "76") (name "unconnected-(U5-2C0-Pad10)") (class "Default")
      (node (ref "U5") (pin "10") (pinfunction "2C0_10") (pintype "unspecified+no_connect"))
    )
    (net (code "77") (name "unconnected-(U5-2C1-Pad11)") (class "Default")
      (node (ref "U5") (pin "11") (pinfunction "2C1_11") (pintype "unspecified+no_connect"))
    )
    (net (code "78") (name "unconnected-(U5-2C2-Pad12)") (class "Default")
      (node (ref "U5") (pin "12") (pinfunction "2C2_12") (pintype "unspecified+no_connect"))
    )
    (net (code "79") (name "unconnected-(U5-2C3-Pad13)") (class "Default")
      (node (ref "U5") (pin "13") (pinfunction "2C3_13") (pintype "unspecified+no_connect"))
    )
    (net (code "80") (name "unconnected-(U5-2G#-Pad15)") (class "Default")
      (node (ref "U5") (pin "15") (pinfunction "2G#_15") (pintype "unspecified+no_connect"))
    )
    (net (code "81") (name "unconnected-(U5-2Y-Pad9)") (class "Default")
      (node (ref "U5") (pin "9") (pinfunction "2Y_9") (pintype "unspecified+no_connect"))
    )
    (net (code "82") (name "unconnected-(U5-GND-Pad8)") (class "Default")
      (node (ref "U5") (pin "8") (pinfunction "GND_8") (pintype "unspecified"))
    )
    (net (code "83") (name "unconnected-(U5-VCC-Pad16)") (class "Default")
      (node (ref "U5") (pin "16") (pinfunction "VCC_16") (pintype "unspecified"))
    )
    (net (code "84") (name "unconnected-(U6-2A-Pad3)") (class "Default")
      (node (ref "U6") (pin "3") (pinfunction "2A_3") (pintype "unspecified+no_connect"))
    )
    (net (code "85") (name "unconnected-(U6-2Y-Pad4)") (class "Default")
      (node (ref "U6") (pin "4") (pinfunction "2Y_4") (pintype "unspecified+no_connect"))
    )
    (net (code "86") (name "unconnected-(U6-3A-Pad5)") (class "Default")
      (node (ref "U6") (pin "5") (pinfunction "3A_5") (pintype "unspecified+no_connect"))
    )
    (net (code "87") (name "unconnected-(U6-3Y-Pad6)") (class "Default")
      (node (ref "U6") (pin "6") (pinfunction "3Y_6") (pintype "unspecified+no_connect"))
    )
    (net (code "88") (name "unconnected-(U6-4A-Pad9)") (class "Default")
      (node (ref "U6") (pin "9") (pinfunction "4A_9") (pintype "unspecified+no_connect"))
    )
    (net (code "89") (name "unconnected-(U6-4Y-Pad8)") (class "Default")
      (node (ref "U6") (pin "8") (pinfunction "4Y_8") (pintype "unspecified+no_connect"))
    )
    (net (code "90") (name "unconnected-(U6-5A-Pad11)") (class "Default")
      (node (ref "U6") (pin "11") (pinfunction "5A_11") (pintype "unspecified+no_connect"))
    )
    (net (code "91") (name "unconnected-(U6-5Y-Pad10)") (class "Default")
      (node (ref "U6") (pin "10") (pinfunction "5Y_10") (pintype "unspecified+no_connect"))
    )
    (net (code "92") (name "unconnected-(U6-6A-Pad13)") (class "Default")
      (node (ref "U6") (pin "13") (pinfunction "6A_13") (pintype "unspecified+no_connect"))
    )
    (net (code "93") (name "unconnected-(U6-6Y-Pad12)") (class "Default")
      (node (ref "U6") (pin "12") (pinfunction "6Y_12") (pintype "unspecified+no_connect"))
    )
    (net (code "94") (name "unconnected-(U6-GND-Pad7)") (class "Default")
      (node (ref "U6") (pin "7") (pinfunction "GND_7") (pintype "unspecified"))
    )
    (net (code "95") (name "unconnected-(U6-VCC-Pad14)") (class "Default")
      (node (ref "U6") (pin "14") (pinfunction "VCC_14") (pintype "unspecified"))
    )
    (net (code "96") (name "unconnected-(U7-GND-Pad10)") (class "Default")
      (node (ref "U7") (pin "10") (pinfunction "GND_10") (pintype "unspecified"))
    )
    (net (code "97") (name "unconnected-(U7-VCC-Pad20)") (class "Default")
      (node (ref "U7") (pin "20") (pinfunction "VCC_20") (pintype "unspecified"))
    )
    (net (code "98") (name "unconnected-(U8-GND-Pad10)") (class "Default")
      (node (ref "U8") (pin "10") (pinfunction "GND_10") (pintype "unspecified"))
    )
    (net (code "99") (name "unconnected-(U8-VCC-Pad20)") (class "Default")
      (node (ref "U8") (pin "20") (pinfunction "VCC_20") (pintype "unspecified"))
    )
    (net (code "100") (name "unconnected-(U9-GND-Pad14)") (class "Default")
      (node (ref "U9") (pin "14") (pinfunction "GND_14") (pintype "unspecified"))
    )
    (net (code "101") (name "unconnected-(U9-VCC-Pad28)") (class "Default")
      (node (ref "U9") (pin "28") (pinfunction "VCC_28") (pintype "unspecified"))
    )
    (net (code "102") (name "unconnected-(U9-nAEN-Pad13)") (class "Default")
      (node (ref "U9") (pin "13") (pinfunction "nAEN_13") (pintype "unspecified"))
    )
    (net (code "103") (name "unconnected-(U9-nBEN-Pad15)") (class "Default")
      (node (ref "U9") (pin "15") (pinfunction "nBEN_15") (pintype "unspecified"))
    )
    (net (code "104") (name "unconnected-(U10-1Y-Pad2)") (class "Default")
      (node (ref "U10") (pin "2") (pinfunction "1Y_2") (pintype "unspecified"))
    )
    (net (code "105") (name "unconnected-(U10-2Y-Pad4)") (class "Default")
      (node (ref "U10") (pin "4") (pinfunction "2Y_4") (pintype "unspecified"))
    )
    (net (code "106") (name "unconnected-(U10-3Y-Pad6)") (class "Default")
      (node (ref "U10") (pin "6") (pinfunction "3Y_6") (pintype "unspecified"))
    )
    (net (code "107") (name "unconnected-(U10-4Y-Pad8)") (class "Default")
      (node (ref "U10") (pin "8") (pinfunction "4Y_8") (pintype "unspecified"))
    )
    (net (code "108") (name "unconnected-(U10-5A-Pad11)") (class "Default")
      (node (ref "U10") (pin "11") (pinfunction "5A_11") (pintype "unspecified"))
    )
    (net (code "109") (name "unconnected-(U10-5Y-Pad10)") (class "Default")
      (node (ref "U10") (pin "10") (pinfunction "5Y_10") (pintype "unspecified"))
    )
    (net (code "110") (name "unconnected-(U10-6A-Pad13)") (class "Default")
      (node (ref "U10") (pin "13") (pinfunction "6A_13") (pintype "unspecified"))
    )
    (net (code "111") (name "unconnected-(U10-6Y-Pad12)") (class "Default")
      (node (ref "U10") (pin "12") (pinfunction "6Y_12") (pintype "unspecified"))
    )
    (net (code "112") (name "unconnected-(U10-GND-Pad7)") (class "Default")
      (node (ref "U10") (pin "7") (pinfunction "GND_7") (pintype "unspecified"))
    )
    (net (code "113") (name "unconnected-(U10-VCC-Pad14)") (class "Default")
      (node (ref "U10") (pin "14") (pinfunction "VCC_14") (pintype "unspecified"))
    )
    (net (code "114") (name "unconnected-(U11-A1-Pad2)") (class "Default")
      (node (ref "U11") (pin "2") (pinfunction "A1_2") (pintype "unspecified"))
    )
    (net (code "115") (name "unconnected-(U11-A2-Pad3)") (class "Default")
      (node (ref "U11") (pin "3") (pinfunction "A2_3") (pintype "unspecified"))
    )
    (net (code "116") (name "unconnected-(U11-A3-Pad4)") (class "Default")
      (node (ref "U11") (pin "4") (pinfunction "A3_4") (pintype "unspecified"))
    )
    (net (code "117") (name "unconnected-(U11-A4-Pad5)") (class "Default")
      (node (ref "U11") (pin "5") (pinfunction "A4_5") (pintype "unspecified"))
    )
    (net (code "118") (name "unconnected-(U11-A5-Pad6)") (class "Default")
      (node (ref "U11") (pin "6") (pinfunction "A5_6") (pintype "unspecified"))
    )
    (net (code "119") (name "unconnected-(U11-A6-Pad7)") (class "Default")
      (node (ref "U11") (pin "7") (pinfunction "A6_7") (pintype "unspecified"))
    )
    (net (code "120") (name "unconnected-(U11-A7-Pad8)") (class "Default")
      (node (ref "U11") (pin "8") (pinfunction "A7_8") (pintype "unspecified"))
    )
    (net (code "121") (name "unconnected-(U11-A8-Pad9)") (class "Default")
      (node (ref "U11") (pin "9") (pinfunction "A8_9") (pintype "unspecified"))
    )
    (net (code "122") (name "unconnected-(U11-GND-Pad10)") (class "Default")
      (node (ref "U11") (pin "10") (pinfunction "GND_10") (pintype "unspecified"))
    )
    (net (code "123") (name "unconnected-(U11-VCC-Pad20)") (class "Default")
      (node (ref "U11") (pin "20") (pinfunction "VCC_20") (pintype "unspecified"))
    )
    (net (code "124") (name "unconnected-(U11-Y1-Pad18)") (class "Default")
      (node (ref "U11") (pin "18") (pinfunction "Y1_18") (pintype "unspecified"))
    )
    (net (code "125") (name "unconnected-(U11-Y2-Pad17)") (class "Default")
      (node (ref "U11") (pin "17") (pinfunction "Y2_17") (pintype "unspecified"))
    )
    (net (code "126") (name "unconnected-(U11-Y3-Pad16)") (class "Default")
      (node (ref "U11") (pin "16") (pinfunction "Y3_16") (pintype "unspecified"))
    )
    (net (code "127") (name "unconnected-(U11-Y4-Pad15)") (class "Default")
      (node (ref "U11") (pin "15") (pinfunction "Y4_15") (pintype "unspecified"))
    )
    (net (code "128") (name "unconnected-(U11-Y5-Pad14)") (class "Default")
      (node (ref "U11") (pin "14") (pinfunction "Y5_14") (pintype "unspecified"))
    )
    (net (code "129") (name "unconnected-(U11-Y6-Pad13)") (class "Default")
      (node (ref "U11") (pin "13") (pinfunction "Y6_13") (pintype "unspecified"))
    )
    (net (code "130") (name "unconnected-(U11-Y7-Pad12)") (class "Default")
      (node (ref "U11") (pin "12") (pinfunction "Y7_12") (pintype "unspecified"))
    )
    (net (code "131") (name "unconnected-(U11-Y8-Pad11)") (class "Default")
      (node (ref "U11") (pin "11") (pinfunction "Y8_11") (pintype "unspecified"))
    )
    (net (code "132") (name "unconnected-(U12-GND-Pad14)") (class "Default")
      (node (ref "U12") (pin "14") (pinfunction "GND_14") (pintype "unspecified"))
    )
    (net (code "133") (name "unconnected-(U12-VCC-Pad28)") (class "Default")
      (node (ref "U12") (pin "28") (pinfunction "VCC_28") (pintype "unspecified"))
    )
    (net (code "134") (name "unconnected-(U12-nAEN-Pad13)") (class "Default")
      (node (ref "U12") (pin "13") (pinfunction "nAEN_13") (pintype "unspecified"))
    )
    (net (code "135") (name "unconnected-(U12-nBEN-Pad15)") (class "Default")
      (node (ref "U12") (pin "15") (pinfunction "nBEN_15") (pintype "unspecified"))
    )
    (net (code "136") (name "unconnected-(U13-GND-Pad14)") (class "Default")
      (node (ref "U13") (pin "14") (pinfunction "GND_14") (pintype "unspecified"))
    )
    (net (code "137") (name "unconnected-(U13-VCC-Pad28)") (class "Default")
      (node (ref "U13") (pin "28") (pinfunction "VCC_28") (pintype "unspecified"))
    )
    (net (code "138") (name "unconnected-(U13-nAEN-Pad13)") (class "Default")
      (node (ref "U13") (pin "13") (pinfunction "nAEN_13") (pintype "unspecified"))
    )
    (net (code "139") (name "unconnected-(U13-nBEN-Pad15)") (class "Default")
      (node (ref "U13") (pin "15") (pinfunction "nBEN_15") (pintype "unspecified"))
    )
    (net (code "140") (name "unconnected-(U14-A1-Pad2)") (class "Default")
      (node (ref "U14") (pin "2") (pinfunction "A1_2") (pintype "unspecified"))
    )
    (net (code "141") (name "unconnected-(U14-A2-Pad3)") (class "Default")
      (node (ref "U14") (pin "3") (pinfunction "A2_3") (pintype "unspecified"))
    )
    (net (code "142") (name "unconnected-(U14-A3-Pad4)") (class "Default")
      (node (ref "U14") (pin "4") (pinfunction "A3_4") (pintype "unspecified"))
    )
    (net (code "143") (name "unconnected-(U14-A4-Pad5)") (class "Default")
      (node (ref "U14") (pin "5") (pinfunction "A4_5") (pintype "unspecified"))
    )
    (net (code "144") (name "unconnected-(U14-A5-Pad6)") (class "Default")
      (node (ref "U14") (pin "6") (pinfunction "A5_6") (pintype "unspecified"))
    )
    (net (code "145") (name "unconnected-(U14-A6-Pad7)") (class "Default")
      (node (ref "U14") (pin "7") (pinfunction "A6_7") (pintype "unspecified"))
    )
    (net (code "146") (name "unconnected-(U14-A7-Pad8)") (class "Default")
      (node (ref "U14") (pin "8") (pinfunction "A7_8") (pintype "unspecified"))
    )
    (net (code "147") (name "unconnected-(U14-A8-Pad9)") (class "Default")
      (node (ref "U14") (pin "9") (pinfunction "A8_9") (pintype "unspecified"))
    )
    (net (code "148") (name "unconnected-(U14-GND-Pad10)") (class "Default")
      (node (ref "U14") (pin "10") (pinfunction "GND_10") (pintype "unspecified"))
    )
    (net (code "149") (name "unconnected-(U14-VCC-Pad20)") (class "Default")
      (node (ref "U14") (pin "20") (pinfunction "VCC_20") (pintype "unspecified"))
    )
    (net (code "150") (name "unconnected-(U14-Y1-Pad18)") (class "Default")
      (node (ref "U14") (pin "18") (pinfunction "Y1_18") (pintype "unspecified"))
    )
    (net (code "151") (name "unconnected-(U14-Y2-Pad17)") (class "Default")
      (node (ref "U14") (pin "17") (pinfunction "Y2_17") (pintype "unspecified"))
    )
    (net (code "152") (name "unconnected-(U14-Y3-Pad16)") (class "Default")
      (node (ref "U14") (pin "16") (pinfunction "Y3_16") (pintype "unspecified"))
    )
    (net (code "153") (name "unconnected-(U14-Y4-Pad15)") (class "Default")
      (node (ref "U14") (pin "15") (pinfunction "Y4_15") (pintype "unspecified"))
    )
    (net (code "154") (name "unconnected-(U14-Y5-Pad14)") (class "Default")
      (node (ref "U14") (pin "14") (pinfunction "Y5_14") (pintype "unspecified"))
    )
    (net (code "155") (name "unconnected-(U14-Y6-Pad13)") (class "Default")
      (node (ref "U14") (pin "13") (pinfunction "Y6_13") (pintype "unspecified"))
    )
    (net (code "156") (name "unconnected-(U14-Y7-Pad12)") (class "Default")
      (node (ref "U14") (pin "12") (pinfunction "Y7_12") (pintype "unspecified"))
    )
    (net (code "157") (name "unconnected-(U14-Y8-Pad11)") (class "Default")
      (node (ref "U14") (pin "11") (pinfunction "Y8_11") (pintype "unspecified"))
    )
    (net (code "158") (name "unconnected-(U15-GND-Pad14)") (class "Default")
      (node (ref "U15") (pin "14") (pinfunction "GND_14") (pintype "unspecified"))
    )
    (net (code "159") (name "unconnected-(U15-VCC-Pad28)") (class "Default")
      (node (ref "U15") (pin "28") (pinfunction "VCC_28") (pintype "unspecified"))
    )
    (net (code "160") (name "unconnected-(U15-nAEN-Pad13)") (class "Default")
      (node (ref "U15") (pin "13") (pinfunction "nAEN_13") (pintype "unspecified"))
    )
    (net (code "161") (name "unconnected-(U15-nBEN-Pad15)") (class "Default")
      (node (ref "U15") (pin "15") (pinfunction "nBEN_15") (pintype "unspecified"))
    )
    (net (code "162") (name "unconnected-(U16-GND-Pad12)") (class "Default")
      (node (ref "U16") (pin "12") (pinfunction "GND_12") (pintype "passive"))
    )
    (net (code "163") (name "unconnected-(U16-S1-Pad9)") (class "Default")
      (node (ref "U16") (pin "9") (pinfunction "S1_9") (pintype "output"))
    )
    (net (code "164") (name "unconnected-(U16-S2-Pad6)") (class "Default")
      (node (ref "U16") (pin "6") (pinfunction "S2_6") (pintype "output"))
    )
    (net (code "165") (name "unconnected-(U16-S3-Pad2)") (class "Default")
      (node (ref "U16") (pin "2") (pinfunction "S3_2") (pintype "output"))
    )
    (net (code "166") (name "unconnected-(U16-S4-Pad15)") (class "Default")
      (node (ref "U16") (pin "15") (pinfunction "S4_15") (pintype "output"))
    )
    (net (code "167") (name "unconnected-(U16-VCC-Pad5)") (class "Default")
      (node (ref "U16") (pin "5") (pinfunction "VCC_5") (pintype "passive"))
    )
    (net (code "168") (name "unconnected-(U17-C4-Pad14)") (class "Default")
      (node (ref "U17") (pin "14") (pinfunction "C4_14") (pintype "output+no_connect"))
    )
    (net (code "169") (name "unconnected-(U17-GND-Pad12)") (class "Default")
      (node (ref "U17") (pin "12") (pinfunction "GND_12") (pintype "passive"))
    )
    (net (code "170") (name "unconnected-(U17-S1-Pad9)") (class "Default")
      (node (ref "U17") (pin "9") (pinfunction "S1_9") (pintype "output"))
    )
    (net (code "171") (name "unconnected-(U17-S2-Pad6)") (class "Default")
      (node (ref "U17") (pin "6") (pinfunction "S2_6") (pintype "output"))
    )
    (net (code "172") (name "unconnected-(U17-S3-Pad2)") (class "Default")
      (node (ref "U17") (pin "2") (pinfunction "S3_2") (pintype "output"))
    )
    (net (code "173") (name "unconnected-(U17-S4-Pad15)") (class "Default")
      (node (ref "U17") (pin "15") (pinfunction "S4_15") (pintype "output"))
    )
    (net (code "174") (name "unconnected-(U17-VCC-Pad5)") (class "Default")
      (node (ref "U17") (pin "5") (pinfunction "VCC_5") (pintype "passive"))
    )
    (net (code "175") (name "unconnected-(U18-1A-Pad1)") (class "Default")
      (node (ref "U18") (pin "1") (pinfunction "1A_1") (pintype "unspecified"))
    )
    (net (code "176") (name "unconnected-(U18-1B-Pad2)") (class "Default")
      (node (ref "U18") (pin "2") (pinfunction "1B_2") (pintype "unspecified"))
    )
    (net (code "177") (name "unconnected-(U18-1Y-Pad3)") (class "Default")
      (node (ref "U18") (pin "3") (pinfunction "1Y_3") (pintype "unspecified"))
    )
    (net (code "178") (name "unconnected-(U18-2A-Pad4)") (class "Default")
      (node (ref "U18") (pin "4") (pinfunction "2A_4") (pintype "unspecified"))
    )
    (net (code "179") (name "unconnected-(U18-2B-Pad5)") (class "Default")
      (node (ref "U18") (pin "5") (pinfunction "2B_5") (pintype "unspecified"))
    )
    (net (code "180") (name "unconnected-(U18-2Y-Pad6)") (class "Default")
      (node (ref "U18") (pin "6") (pinfunction "2Y_6") (pintype "unspecified"))
    )
    (net (code "181") (name "unconnected-(U18-3A-Pad9)") (class "Default")
      (node (ref "U18") (pin "9") (pinfunction "3A_9") (pintype "unspecified"))
    )
    (net (code "182") (name "unconnected-(U18-3B-Pad10)") (class "Default")
      (node (ref "U18") (pin "10") (pinfunction "3B_10") (pintype "unspecified"))
    )
    (net (code "183") (name "unconnected-(U18-3Y-Pad8)") (class "Default")
      (node (ref "U18") (pin "8") (pinfunction "3Y_8") (pintype "unspecified"))
    )
    (net (code "184") (name "unconnected-(U18-4A-Pad12)") (class "Default")
      (node (ref "U18") (pin "12") (pinfunction "4A_12") (pintype "unspecified"))
    )
    (net (code "185") (name "unconnected-(U18-4B-Pad13)") (class "Default")
      (node (ref "U18") (pin "13") (pinfunction "4B_13") (pintype "unspecified"))
    )
    (net (code "186") (name "unconnected-(U18-4Y-Pad11)") (class "Default")
      (node (ref "U18") (pin "11") (pinfunction "4Y_11") (pintype "unspecified"))
    )
    (net (code "187") (name "unconnected-(U18-GND-Pad7)") (class "Default")
      (node (ref "U18") (pin "7") (pinfunction "GND_7") (pintype "unspecified"))
    )
    (net (code "188") (name "unconnected-(U18-VCC-Pad14)") (class "Default")
      (node (ref "U18") (pin "14") (pinfunction "VCC_14") (pintype "unspecified"))
    )
    (net (code "189") (name "unconnected-(U19-1A-Pad1)") (class "Default")
      (node (ref "U19") (pin "1") (pinfunction "1A_1") (pintype "unspecified"))
    )
    (net (code "190") (name "unconnected-(U19-1B-Pad2)") (class "Default")
      (node (ref "U19") (pin "2") (pinfunction "1B_2") (pintype "unspecified"))
    )
    (net (code "191") (name "unconnected-(U19-1Y-Pad3)") (class "Default")
      (node (ref "U19") (pin "3") (pinfunction "1Y_3") (pintype "unspecified"))
    )
    (net (code "192") (name "unconnected-(U19-2A-Pad4)") (class "Default")
      (node (ref "U19") (pin "4") (pinfunction "2A_4") (pintype "unspecified"))
    )
    (net (code "193") (name "unconnected-(U19-2B-Pad5)") (class "Default")
      (node (ref "U19") (pin "5") (pinfunction "2B_5") (pintype "unspecified"))
    )
    (net (code "194") (name "unconnected-(U19-2Y-Pad6)") (class "Default")
      (node (ref "U19") (pin "6") (pinfunction "2Y_6") (pintype "unspecified"))
    )
    (net (code "195") (name "unconnected-(U19-3A-Pad9)") (class "Default")
      (node (ref "U19") (pin "9") (pinfunction "3A_9") (pintype "unspecified"))
    )
    (net (code "196") (name "unconnected-(U19-3B-Pad10)") (class "Default")
      (node (ref "U19") (pin "10") (pinfunction "3B_10") (pintype "unspecified"))
    )
    (net (code "197") (name "unconnected-(U19-3Y-Pad8)") (class "Default")
      (node (ref "U19") (pin "8") (pinfunction "3Y_8") (pintype "unspecified"))
    )
    (net (code "198") (name "unconnected-(U19-4A-Pad12)") (class "Default")
      (node (ref "U19") (pin "12") (pinfunction "4A_12") (pintype "unspecified"))
    )
    (net (code "199") (name "unconnected-(U19-4B-Pad13)") (class "Default")
      (node (ref "U19") (pin "13") (pinfunction "4B_13") (pintype "unspecified"))
    )
    (net (code "200") (name "unconnected-(U19-4Y-Pad11)") (class "Default")
      (node (ref "U19") (pin "11") (pinfunction "4Y_11") (pintype "unspecified"))
    )
    (net (code "201") (name "unconnected-(U19-GND-Pad7)") (class "Default")
      (node (ref "U19") (pin "7") (pinfunction "GND_7") (pintype "unspecified"))
    )
    (net (code "202") (name "unconnected-(U19-VCC-Pad14)") (class "Default")
      (node (ref "U19") (pin "14") (pinfunction "VCC_14") (pintype "unspecified"))
    )
    (net (code "203") (name "unconnected-(U20-1A-Pad1)") (class "Default")
      (node (ref "U20") (pin "1") (pinfunction "1A_1") (pintype "unspecified"))
    )
    (net (code "204") (name "unconnected-(U20-1B-Pad2)") (class "Default")
      (node (ref "U20") (pin "2") (pinfunction "1B_2") (pintype "unspecified"))
    )
    (net (code "205") (name "unconnected-(U20-1Y-Pad3)") (class "Default")
      (node (ref "U20") (pin "3") (pinfunction "1Y_3") (pintype "unspecified"))
    )
    (net (code "206") (name "unconnected-(U20-2A-Pad4)") (class "Default")
      (node (ref "U20") (pin "4") (pinfunction "2A_4") (pintype "unspecified"))
    )
    (net (code "207") (name "unconnected-(U20-2B-Pad5)") (class "Default")
      (node (ref "U20") (pin "5") (pinfunction "2B_5") (pintype "unspecified"))
    )
    (net (code "208") (name "unconnected-(U20-2Y-Pad6)") (class "Default")
      (node (ref "U20") (pin "6") (pinfunction "2Y_6") (pintype "unspecified"))
    )
    (net (code "209") (name "unconnected-(U20-3A-Pad9)") (class "Default")
      (node (ref "U20") (pin "9") (pinfunction "3A_9") (pintype "unspecified"))
    )
    (net (code "210") (name "unconnected-(U20-3B-Pad10)") (class "Default")
      (node (ref "U20") (pin "10") (pinfunction "3B_10") (pintype "unspecified"))
    )
    (net (code "211") (name "unconnected-(U20-3Y-Pad8)") (class "Default")
      (node (ref "U20") (pin "8") (pinfunction "3Y_8") (pintype "unspecified"))
    )
    (net (code "212") (name "unconnected-(U20-4A-Pad12)") (class "Default")
      (node (ref "U20") (pin "12") (pinfunction "4A_12") (pintype "unspecified"))
    )
    (net (code "213") (name "unconnected-(U20-4B-Pad13)") (class "Default")
      (node (ref "U20") (pin "13") (pinfunction "4B_13") (pintype "unspecified"))
    )
    (net (code "214") (name "unconnected-(U20-4Y-Pad11)") (class "Default")
      (node (ref "U20") (pin "11") (pinfunction "4Y_11") (pintype "unspecified"))
    )
    (net (code "215") (name "unconnected-(U20-GND-Pad7)") (class "Default")
      (node (ref "U20") (pin "7") (pinfunction "GND_7") (pintype "unspecified"))
    )
    (net (code "216") (name "unconnected-(U20-VCC-Pad14)") (class "Default")
      (node (ref "U20") (pin "14") (pinfunction "VCC_14") (pintype "unspecified"))
    )
    (net (code "217") (name "unconnected-(U21-1A-Pad1)") (class "Default")
      (node (ref "U21") (pin "1") (pinfunction "1A_1") (pintype "unspecified"))
    )
    (net (code "218") (name "unconnected-(U21-1B-Pad2)") (class "Default")
      (node (ref "U21") (pin "2") (pinfunction "1B_2") (pintype "unspecified"))
    )
    (net (code "219") (name "unconnected-(U21-1Y-Pad3)") (class "Default")
      (node (ref "U21") (pin "3") (pinfunction "1Y_3") (pintype "unspecified"))
    )
    (net (code "220") (name "unconnected-(U21-2A-Pad4)") (class "Default")
      (node (ref "U21") (pin "4") (pinfunction "2A_4") (pintype "unspecified"))
    )
    (net (code "221") (name "unconnected-(U21-2B-Pad5)") (class "Default")
      (node (ref "U21") (pin "5") (pinfunction "2B_5") (pintype "unspecified"))
    )
    (net (code "222") (name "unconnected-(U21-2Y-Pad6)") (class "Default")
      (node (ref "U21") (pin "6") (pinfunction "2Y_6") (pintype "unspecified"))
    )
    (net (code "223") (name "unconnected-(U21-3A-Pad9)") (class "Default")
      (node (ref "U21") (pin "9") (pinfunction "3A_9") (pintype "unspecified"))
    )
    (net (code "224") (name "unconnected-(U21-3B-Pad10)") (class "Default")
      (node (ref "U21") (pin "10") (pinfunction "3B_10") (pintype "unspecified"))
    )
    (net (code "225") (name "unconnected-(U21-3Y-Pad8)") (class "Default")
      (node (ref "U21") (pin "8") (pinfunction "3Y_8") (pintype "unspecified"))
    )
    (net (code "226") (name "unconnected-(U21-4A-Pad12)") (class "Default")
      (node (ref "U21") (pin "12") (pinfunction "4A_12") (pintype "unspecified"))
    )
    (net (code "227") (name "unconnected-(U21-4B-Pad13)") (class "Default")
      (node (ref "U21") (pin "13") (pinfunction "4B_13") (pintype "unspecified"))
    )
    (net (code "228") (name "unconnected-(U21-4Y-Pad11)") (class "Default")
      (node (ref "U21") (pin "11") (pinfunction "4Y_11") (pintype "unspecified"))
    )
    (net (code "229") (name "unconnected-(U21-GND-Pad7)") (class "Default")
      (node (ref "U21") (pin "7") (pinfunction "GND_7") (pintype "unspecified"))
    )
    (net (code "230") (name "unconnected-(U21-VCC-Pad14)") (class "Default")
      (node (ref "U21") (pin "14") (pinfunction "VCC_14") (pintype "unspecified"))
    )
    (net (code "231") (name "unconnected-(U22-1A-Pad1)") (class "Default")
      (node (ref "U22") (pin "1") (pinfunction "1A_1") (pintype "unspecified"))
    )
    (net (code "232") (name "unconnected-(U22-1B-Pad2)") (class "Default")
      (node (ref "U22") (pin "2") (pinfunction "1B_2") (pintype "unspecified"))
    )
    (net (code "233") (name "unconnected-(U22-1Y-Pad3)") (class "Default")
      (node (ref "U22") (pin "3") (pinfunction "1Y_3") (pintype "unspecified"))
    )
    (net (code "234") (name "unconnected-(U22-2A-Pad4)") (class "Default")
      (node (ref "U22") (pin "4") (pinfunction "2A_4") (pintype "unspecified"))
    )
    (net (code "235") (name "unconnected-(U22-2B-Pad5)") (class "Default")
      (node (ref "U22") (pin "5") (pinfunction "2B_5") (pintype "unspecified"))
    )
    (net (code "236") (name "unconnected-(U22-2Y-Pad6)") (class "Default")
      (node (ref "U22") (pin "6") (pinfunction "2Y_6") (pintype "unspecified"))
    )
    (net (code "237") (name "unconnected-(U22-3A-Pad9)") (class "Default")
      (node (ref "U22") (pin "9") (pinfunction "3A_9") (pintype "unspecified"))
    )
    (net (code "238") (name "unconnected-(U22-3B-Pad10)") (class "Default")
      (node (ref "U22") (pin "10") (pinfunction "3B_10") (pintype "unspecified"))
    )
    (net (code "239") (name "unconnected-(U22-3Y-Pad8)") (class "Default")
      (node (ref "U22") (pin "8") (pinfunction "3Y_8") (pintype "unspecified"))
    )
    (net (code "240") (name "unconnected-(U22-4A-Pad12)") (class "Default")
      (node (ref "U22") (pin "12") (pinfunction "4A_12") (pintype "unspecified"))
    )
    (net (code "241") (name "unconnected-(U22-4B-Pad13)") (class "Default")
      (node (ref "U22") (pin "13") (pinfunction "4B_13") (pintype "unspecified"))
    )
    (net (code "242") (name "unconnected-(U22-4Y-Pad11)") (class "Default")
      (node (ref "U22") (pin "11") (pinfunction "4Y_11") (pintype "unspecified"))
    )
    (net (code "243") (name "unconnected-(U22-GND-Pad7)") (class "Default")
      (node (ref "U22") (pin "7") (pinfunction "GND_7") (pintype "unspecified"))
    )
    (net (code "244") (name "unconnected-(U22-VCC-Pad14)") (class "Default")
      (node (ref "U22") (pin "14") (pinfunction "VCC_14") (pintype "unspecified"))
    )
    (net (code "245") (name "unconnected-(U23-1A-Pad1)") (class "Default")
      (node (ref "U23") (pin "1") (pinfunction "1A_1") (pintype "unspecified"))
    )
    (net (code "246") (name "unconnected-(U23-1B-Pad2)") (class "Default")
      (node (ref "U23") (pin "2") (pinfunction "1B_2") (pintype "unspecified"))
    )
    (net (code "247") (name "unconnected-(U23-1Y-Pad3)") (class "Default")
      (node (ref "U23") (pin "3") (pinfunction "1Y_3") (pintype "unspecified"))
    )
    (net (code "248") (name "unconnected-(U23-2A-Pad4)") (class "Default")
      (node (ref "U23") (pin "4") (pinfunction "2A_4") (pintype "unspecified"))
    )
    (net (code "249") (name "unconnected-(U23-2B-Pad5)") (class "Default")
      (node (ref "U23") (pin "5") (pinfunction "2B_5") (pintype "unspecified"))
    )
    (net (code "250") (name "unconnected-(U23-2Y-Pad6)") (class "Default")
      (node (ref "U23") (pin "6") (pinfunction "2Y_6") (pintype "unspecified"))
    )
    (net (code "251") (name "unconnected-(U23-3A-Pad9)") (class "Default")
      (node (ref "U23") (pin "9") (pinfunction "3A_9") (pintype "unspecified"))
    )
    (net (code "252") (name "unconnected-(U23-3B-Pad10)") (class "Default")
      (node (ref "U23") (pin "10") (pinfunction "3B_10") (pintype "unspecified"))
    )
    (net (code "253") (name "unconnected-(U23-3Y-Pad8)") (class "Default")
      (node (ref "U23") (pin "8") (pinfunction "3Y_8") (pintype "unspecified"))
    )
    (net (code "254") (name "unconnected-(U23-4A-Pad12)") (class "Default")
      (node (ref "U23") (pin "12") (pinfunction "4A_12") (pintype "unspecified"))
    )
    (net (code "255") (name "unconnected-(U23-4B-Pad13)") (class "Default")
      (node (ref "U23") (pin "13") (pinfunction "4B_13") (pintype "unspecified"))
    )
    (net (code "256") (name "unconnected-(U23-4Y-Pad11)") (class "Default")
      (node (ref "U23") (pin "11") (pinfunction "4Y_11") (pintype "unspecified"))
    )
    (net (code "257") (name "unconnected-(U23-GND-Pad7)") (class "Default")
      (node (ref "U23") (pin "7") (pinfunction "GND_7") (pintype "unspecified"))
    )
    (net (code "258") (name "unconnected-(U23-VCC-Pad14)") (class "Default")
      (node (ref "U23") (pin "14") (pinfunction "VCC_14") (pintype "unspecified"))
    )
    (net (code "259") (name "unconnected-(U24-GND-Pad8)") (class "Default")
      (node (ref "U24") (pin "8") (pinfunction "GND_8") (pintype "unspecified"))
    )
    (net (code "260") (name "unconnected-(U24-VCC-Pad16)") (class "Default")
      (node (ref "U24") (pin "16") (pinfunction "VCC_16") (pintype "unspecified"))
    )
    (net (code "261") (name "unconnected-(U25-GND-Pad8)") (class "Default")
      (node (ref "U25") (pin "8") (pinfunction "GND_8") (pintype "unspecified"))
    )
    (net (code "262") (name "unconnected-(U25-VCC-Pad16)") (class "Default")
      (node (ref "U25") (pin "16") (pinfunction "VCC_16") (pintype "unspecified"))
    )
    (net (code "263") (name "unconnected-(U26-B-Pad2)") (class "Default")
      (node (ref "U26") (pin "2") (pinfunction "B_2") (pintype "unspecified"))
    )
    (net (code "264") (name "unconnected-(U26-GND-Pad8)") (class "Default")
      (node (ref "U26") (pin "8") (pinfunction "GND_8") (pintype "unspecified"))
    )
    (net (code "265") (name "unconnected-(U26-VCC-Pad16)") (class "Default")
      (node (ref "U26") (pin "16") (pinfunction "VCC_16") (pintype "unspecified"))
    )
    (net (code "266") (name "unconnected-(U27-GND-Pad8)") (class "Default")
      (node (ref "U27") (pin "8") (pinfunction "GND_8") (pintype "unspecified"))
    )
    (net (code "267") (name "unconnected-(U27-VCC-Pad16)") (class "Default")
      (node (ref "U27") (pin "16") (pinfunction "VCC_16") (pintype "unspecified"))
    )
    (net (code "268") (name "unconnected-(U28-1A-Pad2)") (class "Default")
      (node (ref "U28") (pin "2") (pinfunction "1A_2") (pintype "unspecified"))
    )
    (net (code "269") (name "unconnected-(U28-1B-Pad3)") (class "Default")
      (node (ref "U28") (pin "3") (pinfunction "1B_3") (pintype "unspecified"))
    )
    (net (code "270") (name "unconnected-(U28-2A-Pad5)") (class "Default")
      (node (ref "U28") (pin "5") (pinfunction "2A_5") (pintype "unspecified"))
    )
    (net (code "271") (name "unconnected-(U28-2B-Pad6)") (class "Default")
      (node (ref "U28") (pin "6") (pinfunction "2B_6") (pintype "unspecified"))
    )
    (net (code "272") (name "unconnected-(U28-3A-Pad8)") (class "Default")
      (node (ref "U28") (pin "8") (pinfunction "3A_8") (pintype "unspecified"))
    )
    (net (code "273") (name "unconnected-(U28-3B-Pad9)") (class "Default")
      (node (ref "U28") (pin "9") (pinfunction "3B_9") (pintype "unspecified"))
    )
    (net (code "274") (name "unconnected-(U28-4A-Pad11)") (class "Default")
      (node (ref "U28") (pin "11") (pinfunction "4A_11") (pintype "unspecified"))
    )
    (net (code "275") (name "unconnected-(U28-GND-Pad7)") (class "Default")
      (node (ref "U28") (pin "7") (pinfunction "GND_7") (pintype "unspecified"))
    )
    (net (code "276") (name "unconnected-(U28-VCC-Pad14)") (class "Default")
      (node (ref "U28") (pin "14") (pinfunction "VCC_14") (pintype "unspecified"))
    )
    (net (code "277") (name "unconnected-(U29-GND-Pad10)") (class "Default")
      (node (ref "U29") (pin "10") (pinfunction "GND_10") (pintype "unspecified"))
    )
    (net (code "278") (name "unconnected-(U29-VCC-Pad20)") (class "Default")
      (node (ref "U29") (pin "20") (pinfunction "VCC_20") (pintype "unspecified"))
    )
    (net (code "279") (name "unconnected-(U30-2Y-Pad6)") (class "Default")
      (node (ref "U30") (pin "6") (pinfunction "2Y_6") (pintype "unspecified"))
    )
    (net (code "280") (name "unconnected-(U30-4A-Pad12)") (class "Default")
      (node (ref "U30") (pin "12") (pinfunction "4A_12") (pintype "unspecified"))
    )
    (net (code "281") (name "unconnected-(U30-4B-Pad13)") (class "Default")
      (node (ref "U30") (pin "13") (pinfunction "4B_13") (pintype "unspecified"))
    )
    (net (code "282") (name "unconnected-(U30-4Y-Pad11)") (class "Default")
      (node (ref "U30") (pin "11") (pinfunction "4Y_11") (pintype "unspecified"))
    )
    (net (code "283") (name "unconnected-(U30-GND-Pad7)") (class "Default")
      (node (ref "U30") (pin "7") (pinfunction "GND_7") (pintype "unspecified"))
    )
    (net (code "284") (name "unconnected-(U30-VCC-Pad14)") (class "Default")
      (node (ref "U30") (pin "14") (pinfunction "VCC_14") (pintype "unspecified"))
    )
  )
)
